# Schematic_TiN.net
KiCad netlist of a schematic drawn in EasyEDA
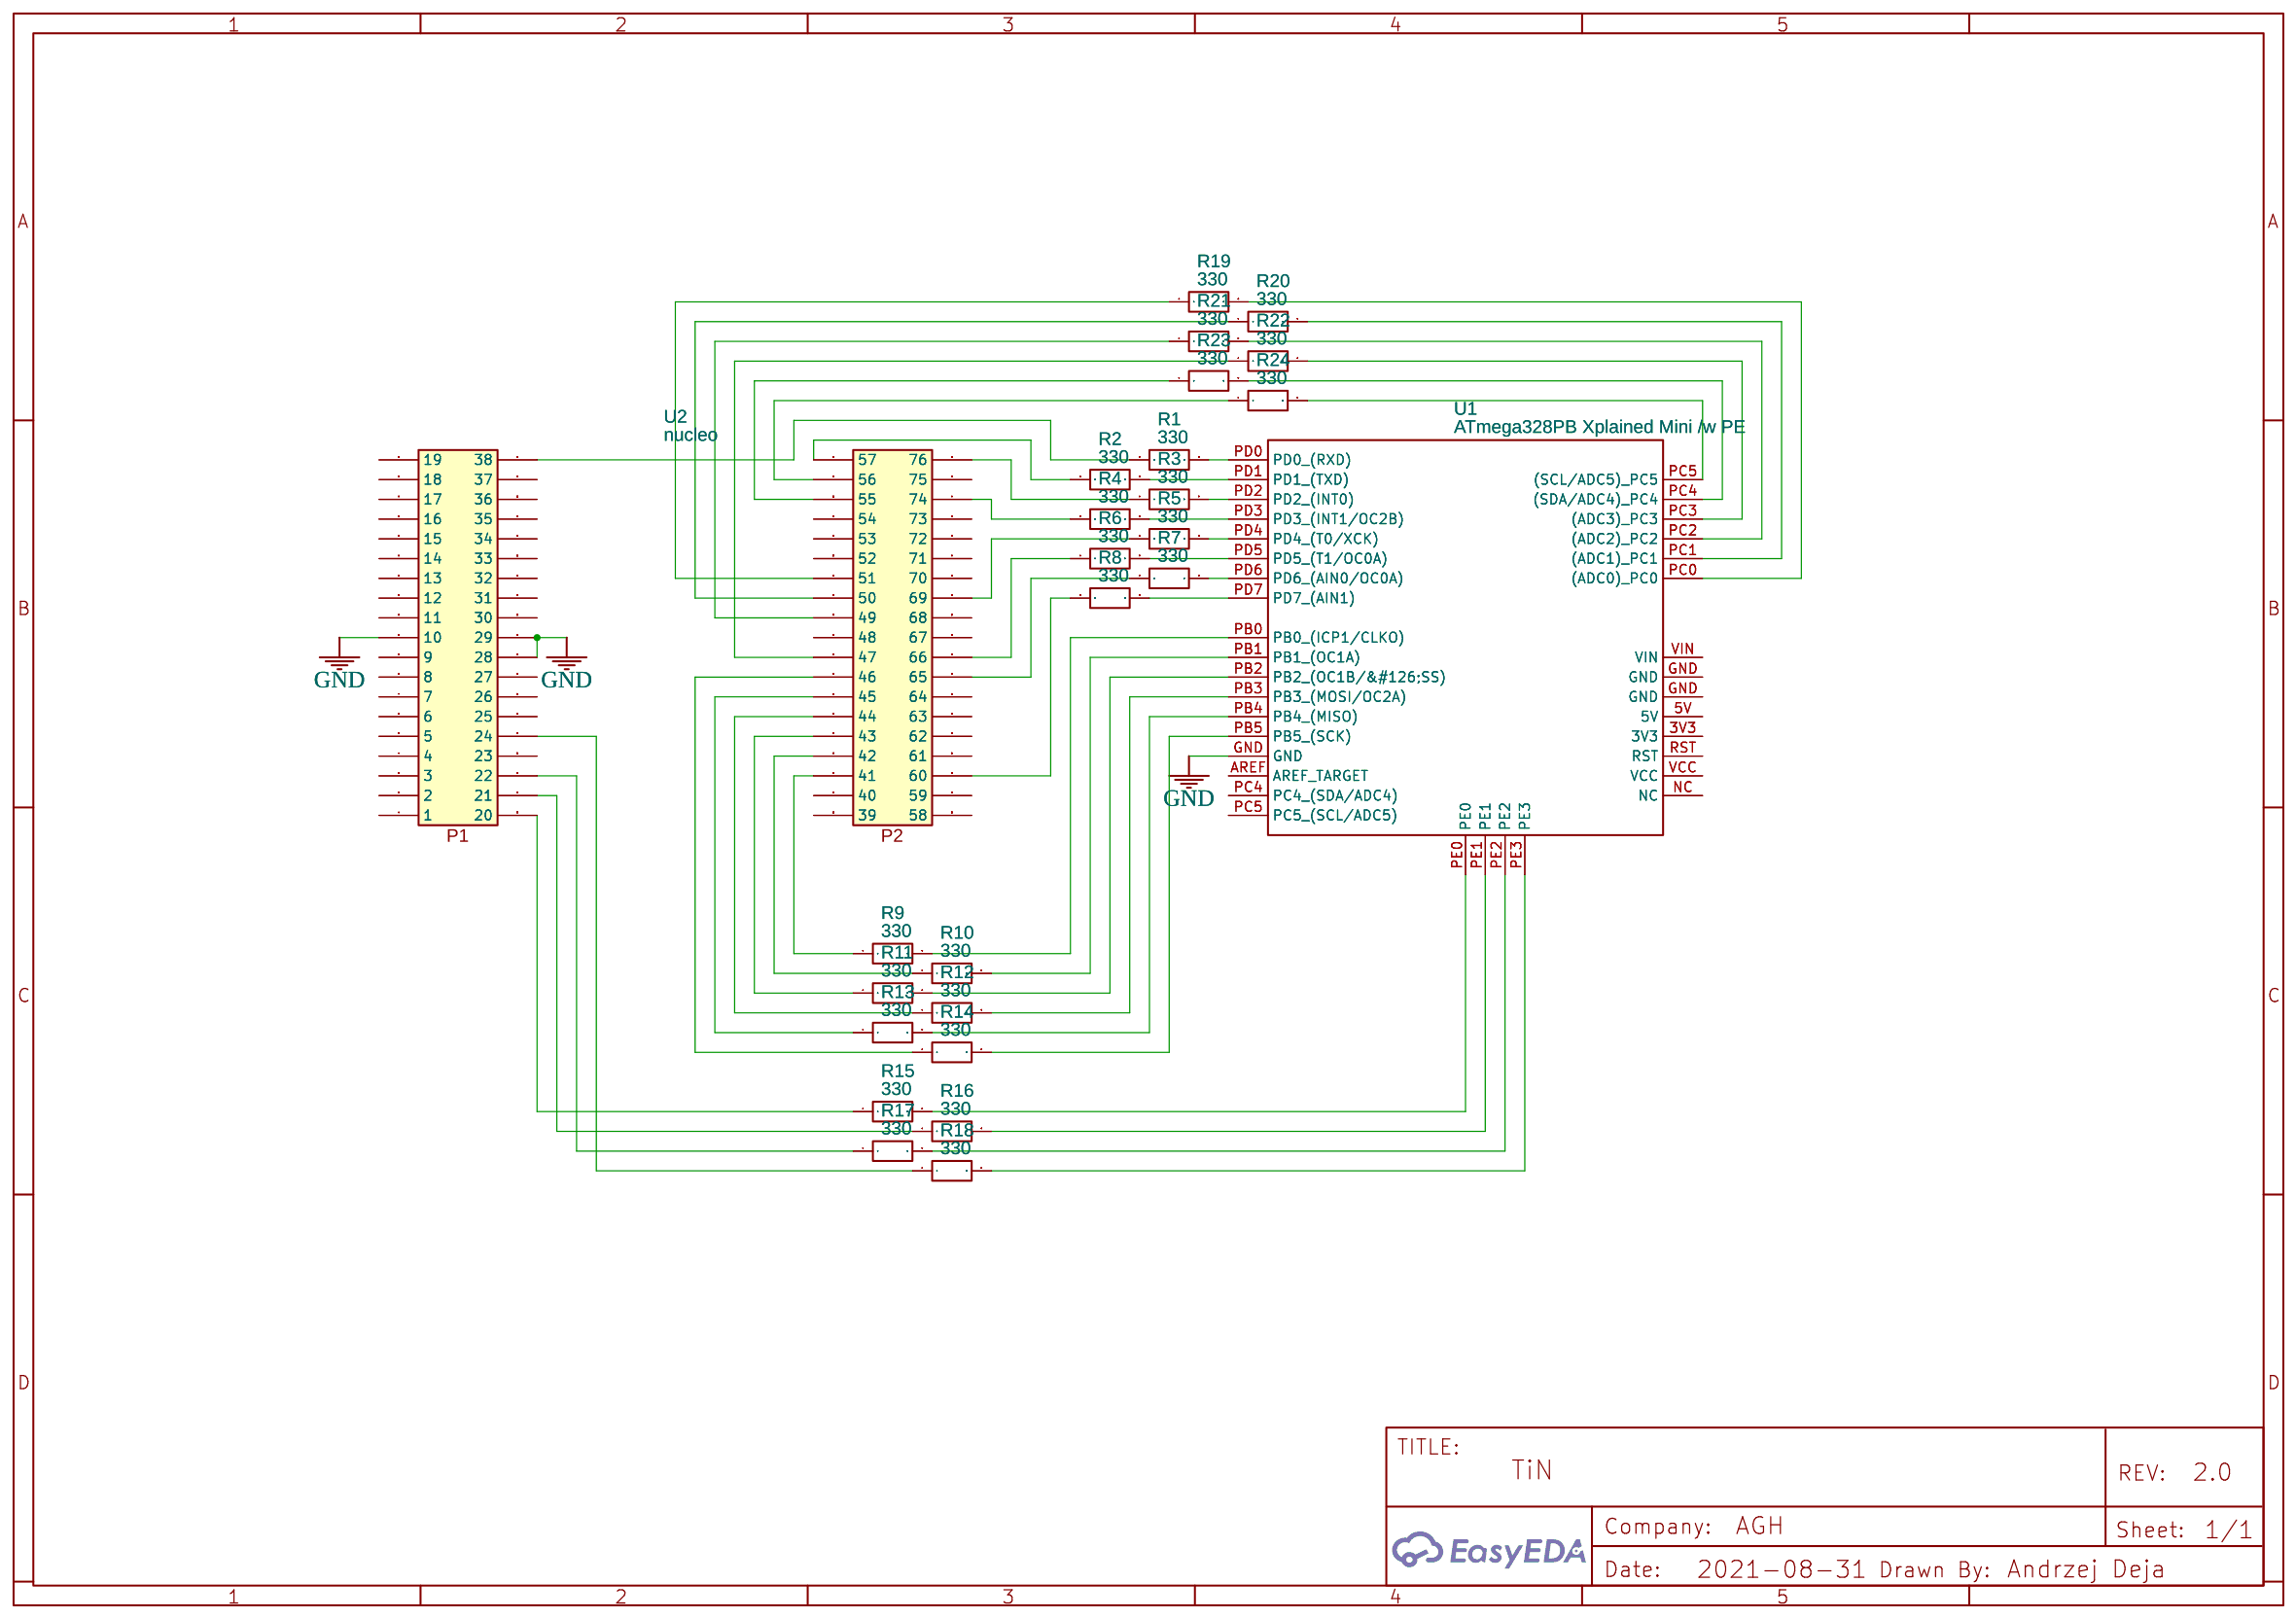
[diagram p0: schematic sheet]

(export (version "E")
  (design (tool "Eeschema 10.0.6"))
  (components
    (comp (ref "R1") (value "330") (libsource (lib "") (part "R_0805_EU")))
    (comp (ref "R2") (value "330") (libsource (lib "") (part "R_0805_EU")))
    (comp (ref "R3") (value "330") (libsource (lib "") (part "R_0805_EU")))
    (comp (ref "R4") (value "330") (libsource (lib "") (part "R_0805_EU")))
    (comp (ref "R5") (value "330") (libsource (lib "") (part "R_0805_EU")))
    (comp (ref "R6") (value "330") (libsource (lib "") (part "R_0805_EU")))
    (comp (ref "R7") (value "330") (libsource (lib "") (part "R_0805_EU")))
    (comp (ref "R8") (value "330") (libsource (lib "") (part "R_0805_EU")))
    (comp (ref "R9") (value "330") (libsource (lib "") (part "R_0805_EU")))
    (comp (ref "R10") (value "330") (libsource (lib "") (part "R_0805_EU")))
    (comp (ref "R11") (value "330") (libsource (lib "") (part "R_0805_EU")))
    (comp (ref "R12") (value "330") (libsource (lib "") (part "R_0805_EU")))
    (comp (ref "R13") (value "330") (libsource (lib "") (part "R_0805_EU")))
    (comp (ref "R14") (value "330") (libsource (lib "") (part "R_0805_EU")))
    (comp (ref "R15") (value "330") (libsource (lib "") (part "R_0805_EU")))
    (comp (ref "R16") (value "330") (libsource (lib "") (part "R_0805_EU")))
    (comp (ref "R17") (value "330") (libsource (lib "") (part "R_0805_EU")))
    (comp (ref "R18") (value "330") (libsource (lib "") (part "R_0805_EU")))
    (comp (ref "R19") (value "330") (libsource (lib "") (part "R_0805_EU")))
    (comp (ref "R20") (value "330") (libsource (lib "") (part "R_0805_EU")))
    (comp (ref "R21") (value "330") (libsource (lib "") (part "R_0805_EU")))
    (comp (ref "R22") (value "330") (libsource (lib "") (part "R_0805_EU")))
    (comp (ref "R23") (value "330") (libsource (lib "") (part "R_0805_EU")))
    (comp (ref "R24") (value "330") (libsource (lib "") (part "R_0805_EU")))
    (comp (ref "U1")
      (value "ATmega328PB Xplained Mini /w PE")
      (libsource (lib "") (part "ATmega328PB Xplained Mini /w PE"))
    )
    (comp (ref "U2") (value "nucleo") (libsource (lib "") (part "nucleo")))
  )
  (nets
    (net (code "1") (name "GND") (class "Default")
      (node (ref "U1") (pin "GND") (pinfunction "GND_GND") (pintype "unspecified"))
      (node (ref "U2") (pin "10") (pinfunction "10_10") (pintype "unspecified"))
      (node (ref "U2") (pin "28") (pinfunction "28_28") (pintype "unspecified"))
      (node (ref "U2") (pin "29") (pinfunction "29_29") (pintype "unspecified"))
    )
    (net (code "2") (name "Net-(R1-Pad1)") (class "Default")
      (node (ref "R1") (pin "1") (pinfunction "1_1") (pintype "unspecified"))
      (node (ref "U2") (pin "38") (pinfunction "38_38") (pintype "unspecified"))
    )
    (net (code "3") (name "Net-(R2-Pad1)") (class "Default")
      (node (ref "R2") (pin "1") (pinfunction "1_1") (pintype "unspecified"))
      (node (ref "U2") (pin "57") (pinfunction "57_57") (pintype "unspecified"))
    )
    (net (code "4") (name "Net-(R3-Pad1)") (class "Default")
      (node (ref "R3") (pin "1") (pinfunction "1_1") (pintype "unspecified"))
      (node (ref "U2") (pin "76") (pinfunction "76_76") (pintype "unspecified"))
    )
    (net (code "5") (name "Net-(R4-Pad1)") (class "Default")
      (node (ref "R4") (pin "1") (pinfunction "1_1") (pintype "unspecified"))
      (node (ref "U2") (pin "74") (pinfunction "74_74") (pintype "unspecified"))
    )
    (net (code "6") (name "Net-(R5-Pad1)") (class "Default")
      (node (ref "R5") (pin "1") (pinfunction "1_1") (pintype "unspecified"))
      (node (ref "U2") (pin "69") (pinfunction "69_69") (pintype "unspecified"))
    )
    (net (code "7") (name "Net-(R6-Pad1)") (class "Default")
      (node (ref "R6") (pin "1") (pinfunction "1_1") (pintype "unspecified"))
      (node (ref "U2") (pin "66") (pinfunction "66_66") (pintype "unspecified"))
    )
    (net (code "8") (name "Net-(R7-Pad1)") (class "Default")
      (node (ref "R7") (pin "1") (pinfunction "1_1") (pintype "unspecified"))
      (node (ref "U2") (pin "65") (pinfunction "65_65") (pintype "unspecified"))
    )
    (net (code "9") (name "Net-(R8-Pad1)") (class "Default")
      (node (ref "R8") (pin "1") (pinfunction "1_1") (pintype "unspecified"))
      (node (ref "U2") (pin "60") (pinfunction "60_60") (pintype "unspecified"))
    )
    (net (code "10") (name "Net-(R9-Pad1)") (class "Default")
      (node (ref "R9") (pin "1") (pinfunction "1_1") (pintype "unspecified"))
      (node (ref "U2") (pin "41") (pinfunction "41_41") (pintype "unspecified"))
    )
    (net (code "11") (name "Net-(R10-Pad1)") (class "Default")
      (node (ref "R10") (pin "1") (pinfunction "1_1") (pintype "unspecified"))
      (node (ref "U2") (pin "42") (pinfunction "42_42") (pintype "unspecified"))
    )
    (net (code "12") (name "Net-(R11-Pad1)") (class "Default")
      (node (ref "R11") (pin "1") (pinfunction "1_1") (pintype "unspecified"))
      (node (ref "U2") (pin "43") (pinfunction "43_43") (pintype "unspecified"))
    )
    (net (code "13") (name "Net-(R12-Pad1)") (class "Default")
      (node (ref "R12") (pin "1") (pinfunction "1_1") (pintype "unspecified"))
      (node (ref "U2") (pin "44") (pinfunction "44_44") (pintype "unspecified"))
    )
    (net (code "14") (name "Net-(R13-Pad1)") (class "Default")
      (node (ref "R13") (pin "1") (pinfunction "1_1") (pintype "unspecified"))
      (node (ref "U2") (pin "45") (pinfunction "45_45") (pintype "unspecified"))
    )
    (net (code "15") (name "Net-(R14-Pad1)") (class "Default")
      (node (ref "R14") (pin "1") (pinfunction "1_1") (pintype "unspecified"))
      (node (ref "U2") (pin "46") (pinfunction "46_46") (pintype "unspecified"))
    )
    (net (code "16") (name "Net-(R15-Pad1)") (class "Default")
      (node (ref "R15") (pin "1") (pinfunction "1_1") (pintype "unspecified"))
      (node (ref "U2") (pin "20") (pinfunction "20_20") (pintype "unspecified"))
    )
    (net (code "17") (name "Net-(R15-Pad2)") (class "Default")
      (node (ref "R15") (pin "2") (pinfunction "2_2") (pintype "unspecified"))
      (node (ref "U1") (pin "PE0") (pinfunction "PE0_PE0") (pintype "unspecified"))
    )
    (net (code "18") (name "Net-(R16-Pad1)") (class "Default")
      (node (ref "R16") (pin "1") (pinfunction "1_1") (pintype "unspecified"))
      (node (ref "U2") (pin "21") (pinfunction "21_21") (pintype "unspecified"))
    )
    (net (code "19") (name "Net-(R16-Pad2)") (class "Default")
      (node (ref "R16") (pin "2") (pinfunction "2_2") (pintype "unspecified"))
      (node (ref "U1") (pin "PE1") (pinfunction "PE1_PE1") (pintype "unspecified"))
    )
    (net (code "20") (name "Net-(R17-Pad1)") (class "Default")
      (node (ref "R17") (pin "1") (pinfunction "1_1") (pintype "unspecified"))
      (node (ref "U2") (pin "22") (pinfunction "22_22") (pintype "unspecified"))
    )
    (net (code "21") (name "Net-(R17-Pad2)") (class "Default")
      (node (ref "R17") (pin "2") (pinfunction "2_2") (pintype "unspecified"))
      (node (ref "U1") (pin "PE2") (pinfunction "PE2_PE2") (pintype "unspecified"))
    )
    (net (code "22") (name "Net-(R18-Pad1)") (class "Default")
      (node (ref "R18") (pin "1") (pinfunction "1_1") (pintype "unspecified"))
      (node (ref "U2") (pin "24") (pinfunction "24_24") (pintype "unspecified"))
    )
    (net (code "23") (name "Net-(R18-Pad2)") (class "Default")
      (node (ref "R18") (pin "2") (pinfunction "2_2") (pintype "unspecified"))
      (node (ref "U1") (pin "PE3") (pinfunction "PE3_PE3") (pintype "unspecified"))
    )
    (net (code "24") (name "Net-(R19-Pad1)") (class "Default")
      (node (ref "R19") (pin "1") (pinfunction "1_1") (pintype "unspecified"))
      (node (ref "U2") (pin "51") (pinfunction "51_51") (pintype "unspecified"))
    )
    (net (code "25") (name "Net-(R20-Pad1)") (class "Default")
      (node (ref "R20") (pin "1") (pinfunction "1_1") (pintype "unspecified"))
      (node (ref "U2") (pin "50") (pinfunction "50_50") (pintype "unspecified"))
    )
    (net (code "26") (name "Net-(R21-Pad1)") (class "Default")
      (node (ref "R21") (pin "1") (pinfunction "1_1") (pintype "unspecified"))
      (node (ref "U2") (pin "49") (pinfunction "49_49") (pintype "unspecified"))
    )
    (net (code "27") (name "Net-(R22-Pad1)") (class "Default")
      (node (ref "R22") (pin "1") (pinfunction "1_1") (pintype "unspecified"))
      (node (ref "U2") (pin "47") (pinfunction "47_47") (pintype "unspecified"))
    )
    (net (code "28") (name "Net-(R23-Pad1)") (class "Default")
      (node (ref "R23") (pin "1") (pinfunction "1_1") (pintype "unspecified"))
      (node (ref "U2") (pin "55") (pinfunction "55_55") (pintype "unspecified"))
    )
    (net (code "29") (name "Net-(R24-Pad1)") (class "Default")
      (node (ref "R24") (pin "1") (pinfunction "1_1") (pintype "unspecified"))
      (node (ref "U2") (pin "56") (pinfunction "56_56") (pintype "unspecified"))
    )
    (net (code "30") (name "Net-(U1-(ADC0)_PC0)") (class "Default")
      (node (ref "R19") (pin "2") (pinfunction "2_2") (pintype "unspecified"))
      (node (ref "U1") (pin "PC0") (pinfunction "(ADC0)_PC0_PC0") (pintype "unspecified"))
    )
    (net (code "31") (name "Net-(U1-(ADC1)_PC1)") (class "Default")
      (node (ref "R20") (pin "2") (pinfunction "2_2") (pintype "unspecified"))
      (node (ref "U1") (pin "PC1") (pinfunction "(ADC1)_PC1_PC1") (pintype "unspecified"))
    )
    (net (code "32") (name "Net-(U1-(ADC2)_PC2)") (class "Default")
      (node (ref "R21") (pin "2") (pinfunction "2_2") (pintype "unspecified"))
      (node (ref "U1") (pin "PC2") (pinfunction "(ADC2)_PC2_PC2") (pintype "unspecified"))
    )
    (net (code "33") (name "Net-(U1-(ADC3)_PC3)") (class "Default")
      (node (ref "R22") (pin "2") (pinfunction "2_2") (pintype "unspecified"))
      (node (ref "U1") (pin "PC3") (pinfunction "(ADC3)_PC3_PC3") (pintype "unspecified"))
    )
    (net (code "34") (name "Net-(U1-(SCL{slash}ADC5)_PC5)") (class "Default")
      (node (ref "R24") (pin "2") (pinfunction "2_2") (pintype "unspecified"))
      (node (ref "U1") (pin "PC5") (pinfunction "(SCL/ADC5)_PC5_PC5") (pintype "unspecified"))
    )
    (net (code "35") (name "Net-(U1-(SDA{slash}ADC4)_PC4)") (class "Default")
      (node (ref "R23") (pin "2") (pinfunction "2_2") (pintype "unspecified"))
      (node (ref "U1") (pin "PC4") (pinfunction "(SDA/ADC4)_PC4_PC4") (pintype "unspecified"))
    )
    (net (code "36") (name "Net-(U1-PB0_(ICP1{slash}CLKO))") (class "Default")
      (node (ref "R9") (pin "2") (pinfunction "2_2") (pintype "unspecified"))
      (node (ref "U1") (pin "PB0") (pinfunction "PB0_(ICP1/CLKO)_PB0") (pintype "unspecified"))
    )
    (net (code "37") (name "Net-(U1-PB1_(OC1A))") (class "Default")
      (node (ref "R10") (pin "2") (pinfunction "2_2") (pintype "unspecified"))
      (node (ref "U1") (pin "PB1") (pinfunction "PB1_(OC1A)_PB1") (pintype "unspecified"))
    )
    (net (code "38") (name "Net-(U1-PB2_(OC1B{slash}&#126;SS))") (class "Default")
      (node (ref "R11") (pin "2") (pinfunction "2_2") (pintype "unspecified"))
      (node (ref "U1") (pin "PB2") (pinfunction "PB2_(OC1B/&#126;SS)_PB2") (pintype "unspecified"))
    )
    (net (code "39") (name "Net-(U1-PB3_(MOSI{slash}OC2A))") (class "Default")
      (node (ref "R12") (pin "2") (pinfunction "2_2") (pintype "unspecified"))
      (node (ref "U1") (pin "PB3") (pinfunction "PB3_(MOSI/OC2A)_PB3") (pintype "unspecified"))
    )
    (net (code "40") (name "Net-(U1-PB4_(MISO))") (class "Default")
      (node (ref "R13") (pin "2") (pinfunction "2_2") (pintype "unspecified"))
      (node (ref "U1") (pin "PB4") (pinfunction "PB4_(MISO)_PB4") (pintype "unspecified"))
    )
    (net (code "41") (name "Net-(U1-PB5_(SCK))") (class "Default")
      (node (ref "R14") (pin "2") (pinfunction "2_2") (pintype "unspecified"))
      (node (ref "U1") (pin "PB5") (pinfunction "PB5_(SCK)_PB5") (pintype "unspecified"))
    )
    (net (code "42") (name "Net-(U1-PD0_(RXD))") (class "Default")
      (node (ref "R1") (pin "2") (pinfunction "2_2") (pintype "unspecified"))
      (node (ref "U1") (pin "PD0") (pinfunction "PD0_(RXD)_PD0") (pintype "unspecified"))
    )
    (net (code "43") (name "Net-(U1-PD1_(TXD))") (class "Default")
      (node (ref "R2") (pin "2") (pinfunction "2_2") (pintype "unspecified"))
      (node (ref "U1") (pin "PD1") (pinfunction "PD1_(TXD)_PD1") (pintype "unspecified"))
    )
    (net (code "44") (name "Net-(U1-PD2_(INT0))") (class "Default")
      (node (ref "R3") (pin "2") (pinfunction "2_2") (pintype "unspecified"))
      (node (ref "U1") (pin "PD2") (pinfunction "PD2_(INT0)_PD2") (pintype "unspecified"))
    )
    (net (code "45") (name "Net-(U1-PD3_(INT1{slash}OC2B))") (class "Default")
      (node (ref "R4") (pin "2") (pinfunction "2_2") (pintype "unspecified"))
      (node (ref "U1") (pin "PD3") (pinfunction "PD3_(INT1/OC2B)_PD3") (pintype "unspecified"))
    )
    (net (code "46") (name "Net-(U1-PD4_(T0{slash}XCK))") (class "Default")
      (node (ref "R5") (pin "2") (pinfunction "2_2") (pintype "unspecified"))
      (node (ref "U1") (pin "PD4") (pinfunction "PD4_(T0/XCK)_PD4") (pintype "unspecified"))
    )
    (net (code "47") (name "Net-(U1-PD5_(T1{slash}OC0A))") (class "Default")
      (node (ref "R6") (pin "2") (pinfunction "2_2") (pintype "unspecified"))
      (node (ref "U1") (pin "PD5") (pinfunction "PD5_(T1/OC0A)_PD5") (pintype "unspecified"))
    )
    (net (code "48") (name "Net-(U1-PD6_(AIN0{slash}OC0A))") (class "Default")
      (node (ref "R7") (pin "2") (pinfunction "2_2") (pintype "unspecified"))
      (node (ref "U1") (pin "PD6") (pinfunction "PD6_(AIN0/OC0A)_PD6") (pintype "unspecified"))
    )
    (net (code "49") (name "Net-(U1-PD7_(AIN1))") (class "Default")
      (node (ref "R8") (pin "2") (pinfunction "2_2") (pintype "unspecified"))
      (node (ref "U1") (pin "PD7") (pinfunction "PD7_(AIN1)_PD7") (pintype "unspecified"))
    )
    (net (code "50") (name "unconnected-(U1-AREF_TARGET-PadAREF)") (class "Default")
      (node (ref "U1") (pin "AREF") (pinfunction "AREF_TARGET_AREF") (pintype "unspecified"))
    )
    (net (code "51") (name "unconnected-(U1-PC4_(SDA{slash}ADC4)-PadPC4)") (class "Default")
      (node (ref "U1") (pin "PC4") (pinfunction "PC4_(SDA/ADC4)_PC4") (pintype "unspecified"))
    )
    (net (code "52") (name "unconnected-(U1-PC5_(SCL{slash}ADC5)-PadPC5)") (class "Default")
      (node (ref "U1") (pin "PC5") (pinfunction "PC5_(SCL/ADC5)_PC5") (pintype "unspecified"))
    )
    (net (code "53") (name "unconnected-(U1-Pad3V3)") (class "Default")
      (node (ref "U1") (pin "3V3") (pinfunction "3V3_3V3") (pintype "unspecified"))
    )
    (net (code "54") (name "unconnected-(U1-Pad5V)") (class "Default")
      (node (ref "U1") (pin "5V") (pinfunction "5V_5V") (pintype "unspecified"))
    )
    (net (code "55") (name "unconnected-(U1-PadGND)") (class "Default")
      (node (ref "U1") (pin "GND") (pinfunction "GND_GND") (pintype "unspecified"))
    )
    (net (code "56") (name "unconnected-(U1-PadGND)_1") (class "Default")
      (node (ref "U1") (pin "GND") (pinfunction "GND_GND") (pintype "unspecified"))
    )
    (net (code "57") (name "unconnected-(U1-PadNC)") (class "Default")
      (node (ref "U1") (pin "NC") (pinfunction "NC_NC") (pintype "unspecified"))
    )
    (net (code "58") (name "unconnected-(U1-PadRST)") (class "Default")
      (node (ref "U1") (pin "RST") (pinfunction "RST_RST") (pintype "unspecified"))
    )
    (net (code "59") (name "unconnected-(U1-PadVCC)") (class "Default")
      (node (ref "U1") (pin "VCC") (pinfunction "VCC_VCC") (pintype "unspecified"))
    )
    (net (code "60") (name "unconnected-(U1-PadVIN)") (class "Default")
      (node (ref "U1") (pin "VIN") (pinfunction "VIN_VIN") (pintype "unspecified"))
    )
    (net (code "61") (name "unconnected-(U2-Pad1)") (class "Default")
      (node (ref "U2") (pin "1") (pinfunction "1_1") (pintype "unspecified"))
    )
    (net (code "62") (name "unconnected-(U2-Pad2)") (class "Default")
      (node (ref "U2") (pin "2") (pinfunction "2_2") (pintype "unspecified"))
    )
    (net (code "63") (name "unconnected-(U2-Pad3)") (class "Default")
      (node (ref "U2") (pin "3") (pinfunction "3_3") (pintype "unspecified"))
    )
    (net (code "64") (name "unconnected-(U2-Pad4)") (class "Default")
      (node (ref "U2") (pin "4") (pinfunction "4_4") (pintype "unspecified"))
    )
    (net (code "65") (name "unconnected-(U2-Pad5)") (class "Default")
      (node (ref "U2") (pin "5") (pinfunction "5_5") (pintype "unspecified"))
    )
    (net (code "66") (name "unconnected-(U2-Pad6)") (class "Default")
      (node (ref "U2") (pin "6") (pinfunction "6_6") (pintype "unspecified"))
    )
    (net (code "67") (name "unconnected-(U2-Pad7)") (class "Default")
      (node (ref "U2") (pin "7") (pinfunction "7_7") (pintype "unspecified"))
    )
    (net (code "68") (name "unconnected-(U2-Pad8)") (class "Default")
      (node (ref "U2") (pin "8") (pinfunction "8_8") (pintype "unspecified"))
    )
    (net (code "69") (name "unconnected-(U2-Pad9)") (class "Default")
      (node (ref "U2") (pin "9") (pinfunction "9_9") (pintype "unspecified"))
    )
    (net (code "70") (name "unconnected-(U2-Pad11)") (class "Default")
      (node (ref "U2") (pin "11") (pinfunction "11_11") (pintype "unspecified"))
    )
    (net (code "71") (name "unconnected-(U2-Pad12)") (class "Default")
      (node (ref "U2") (pin "12") (pinfunction "12_12") (pintype "unspecified"))
    )
    (net (code "72") (name "unconnected-(U2-Pad13)") (class "Default")
      (node (ref "U2") (pin "13") (pinfunction "13_13") (pintype "unspecified"))
    )
    (net (code "73") (name "unconnected-(U2-Pad14)") (class "Default")
      (node (ref "U2") (pin "14") (pinfunction "14_14") (pintype "unspecified"))
    )
    (net (code "74") (name "unconnected-(U2-Pad15)") (class "Default")
      (node (ref "U2") (pin "15") (pinfunction "15_15") (pintype "unspecified"))
    )
    (net (code "75") (name "unconnected-(U2-Pad16)") (class "Default")
      (node (ref "U2") (pin "16") (pinfunction "16_16") (pintype "unspecified"))
    )
    (net (code "76") (name "unconnected-(U2-Pad17)") (class "Default")
      (node (ref "U2") (pin "17") (pinfunction "17_17") (pintype "unspecified"))
    )
    (net (code "77") (name "unconnected-(U2-Pad18)") (class "Default")
      (node (ref "U2") (pin "18") (pinfunction "18_18") (pintype "unspecified"))
    )
    (net (code "78") (name "unconnected-(U2-Pad19)") (class "Default")
      (node (ref "U2") (pin "19") (pinfunction "19_19") (pintype "unspecified"))
    )
    (net (code "79") (name "unconnected-(U2-Pad23)") (class "Default")
      (node (ref "U2") (pin "23") (pinfunction "23_23") (pintype "unspecified"))
    )
    (net (code "80") (name "unconnected-(U2-Pad25)") (class "Default")
      (node (ref "U2") (pin "25") (pinfunction "25_25") (pintype "unspecified"))
    )
    (net (code "81") (name "unconnected-(U2-Pad26)") (class "Default")
      (node (ref "U2") (pin "26") (pinfunction "26_26") (pintype "unspecified"))
    )
    (net (code "82") (name "unconnected-(U2-Pad27)") (class "Default")
      (node (ref "U2") (pin "27") (pinfunction "27_27") (pintype "unspecified"))
    )
    (net (code "83") (name "unconnected-(U2-Pad30)") (class "Default")
      (node (ref "U2") (pin "30") (pinfunction "30_30") (pintype "unspecified"))
    )
    (net (code "84") (name "unconnected-(U2-Pad31)") (class "Default")
      (node (ref "U2") (pin "31") (pinfunction "31_31") (pintype "unspecified"))
    )
    (net (code "85") (name "unconnected-(U2-Pad32)") (class "Default")
      (node (ref "U2") (pin "32") (pinfunction "32_32") (pintype "unspecified"))
    )
    (net (code "86") (name "unconnected-(U2-Pad33)") (class "Default")
      (node (ref "U2") (pin "33") (pinfunction "33_33") (pintype "unspecified"))
    )
    (net (code "87") (name "unconnected-(U2-Pad34)") (class "Default")
      (node (ref "U2") (pin "34") (pinfunction "34_34") (pintype "unspecified"))
    )
    (net (code "88") (name "unconnected-(U2-Pad35)") (class "Default")
      (node (ref "U2") (pin "35") (pinfunction "35_35") (pintype "unspecified"))
    )
    (net (code "89") (name "unconnected-(U2-Pad36)") (class "Default")
      (node (ref "U2") (pin "36") (pinfunction "36_36") (pintype "unspecified"))
    )
    (net (code "90") (name "unconnected-(U2-Pad37)") (class "Default")
      (node (ref "U2") (pin "37") (pinfunction "37_37") (pintype "unspecified"))
    )
    (net (code "91") (name "unconnected-(U2-Pad39)") (class "Default")
      (node (ref "U2") (pin "39") (pinfunction "39_39") (pintype "unspecified"))
    )
    (net (code "92") (name "unconnected-(U2-Pad40)") (class "Default")
      (node (ref "U2") (pin "40") (pinfunction "40_40") (pintype "unspecified"))
    )
    (net (code "93") (name "unconnected-(U2-Pad48)") (class "Default")
      (node (ref "U2") (pin "48") (pinfunction "48_48") (pintype "unspecified"))
    )
    (net (code "94") (name "unconnected-(U2-Pad52)") (class "Default")
      (node (ref "U2") (pin "52") (pinfunction "52_52") (pintype "unspecified"))
    )
    (net (code "95") (name "unconnected-(U2-Pad53)") (class "Default")
      (node (ref "U2") (pin "53") (pinfunction "53_53") (pintype "unspecified"))
    )
    (net (code "96") (name "unconnected-(U2-Pad54)") (class "Default")
      (node (ref "U2") (pin "54") (pinfunction "54_54") (pintype "unspecified"))
    )
    (net (code "97") (name "unconnected-(U2-Pad58)") (class "Default")
      (node (ref "U2") (pin "58") (pinfunction "58_58") (pintype "unspecified"))
    )
    (net (code "98") (name "unconnected-(U2-Pad59)") (class "Default")
      (node (ref "U2") (pin "59") (pinfunction "59_59") (pintype "unspecified"))
    )
    (net (code "99") (name "unconnected-(U2-Pad61)") (class "Default")
      (node (ref "U2") (pin "61") (pinfunction "61_61") (pintype "unspecified"))
    )
    (net (code "100") (name "unconnected-(U2-Pad62)") (class "Default")
      (node (ref "U2") (pin "62") (pinfunction "62_62") (pintype "unspecified"))
    )
    (net (code "101") (name "unconnected-(U2-Pad63)") (class "Default")
      (node (ref "U2") (pin "63") (pinfunction "63_63") (pintype "unspecified"))
    )
    (net (code "102") (name "unconnected-(U2-Pad64)") (class "Default")
      (node (ref "U2") (pin "64") (pinfunction "64_64") (pintype "unspecified"))
    )
    (net (code "103") (name "unconnected-(U2-Pad67)") (class "Default")
      (node (ref "U2") (pin "67") (pinfunction "67_67") (pintype "unspecified"))
    )
    (net (code "104") (name "unconnected-(U2-Pad68)") (class "Default")
      (node (ref "U2") (pin "68") (pinfunction "68_68") (pintype "unspecified"))
    )
    (net (code "105") (name "unconnected-(U2-Pad70)") (class "Default")
      (node (ref "U2") (pin "70") (pinfunction "70_70") (pintype "unspecified"))
    )
    (net (code "106") (name "unconnected-(U2-Pad71)") (class "Default")
      (node (ref "U2") (pin "71") (pinfunction "71_71") (pintype "unspecified"))
    )
    (net (code "107") (name "unconnected-(U2-Pad72)") (class "Default")
      (node (ref "U2") (pin "72") (pinfunction "72_72") (pintype "unspecified"))
    )
    (net (code "108") (name "unconnected-(U2-Pad73)") (class "Default")
      (node (ref "U2") (pin "73") (pinfunction "73_73") (pintype "unspecified"))
    )
    (net (code "109") (name "unconnected-(U2-Pad75)") (class "Default")
      (node (ref "U2") (pin "75") (pinfunction "75_75") (pintype "unspecified"))
    )
  )
)
